# Cyusb3314_Power.net
KiCad netlist of a schematic drawn in Altium Designer
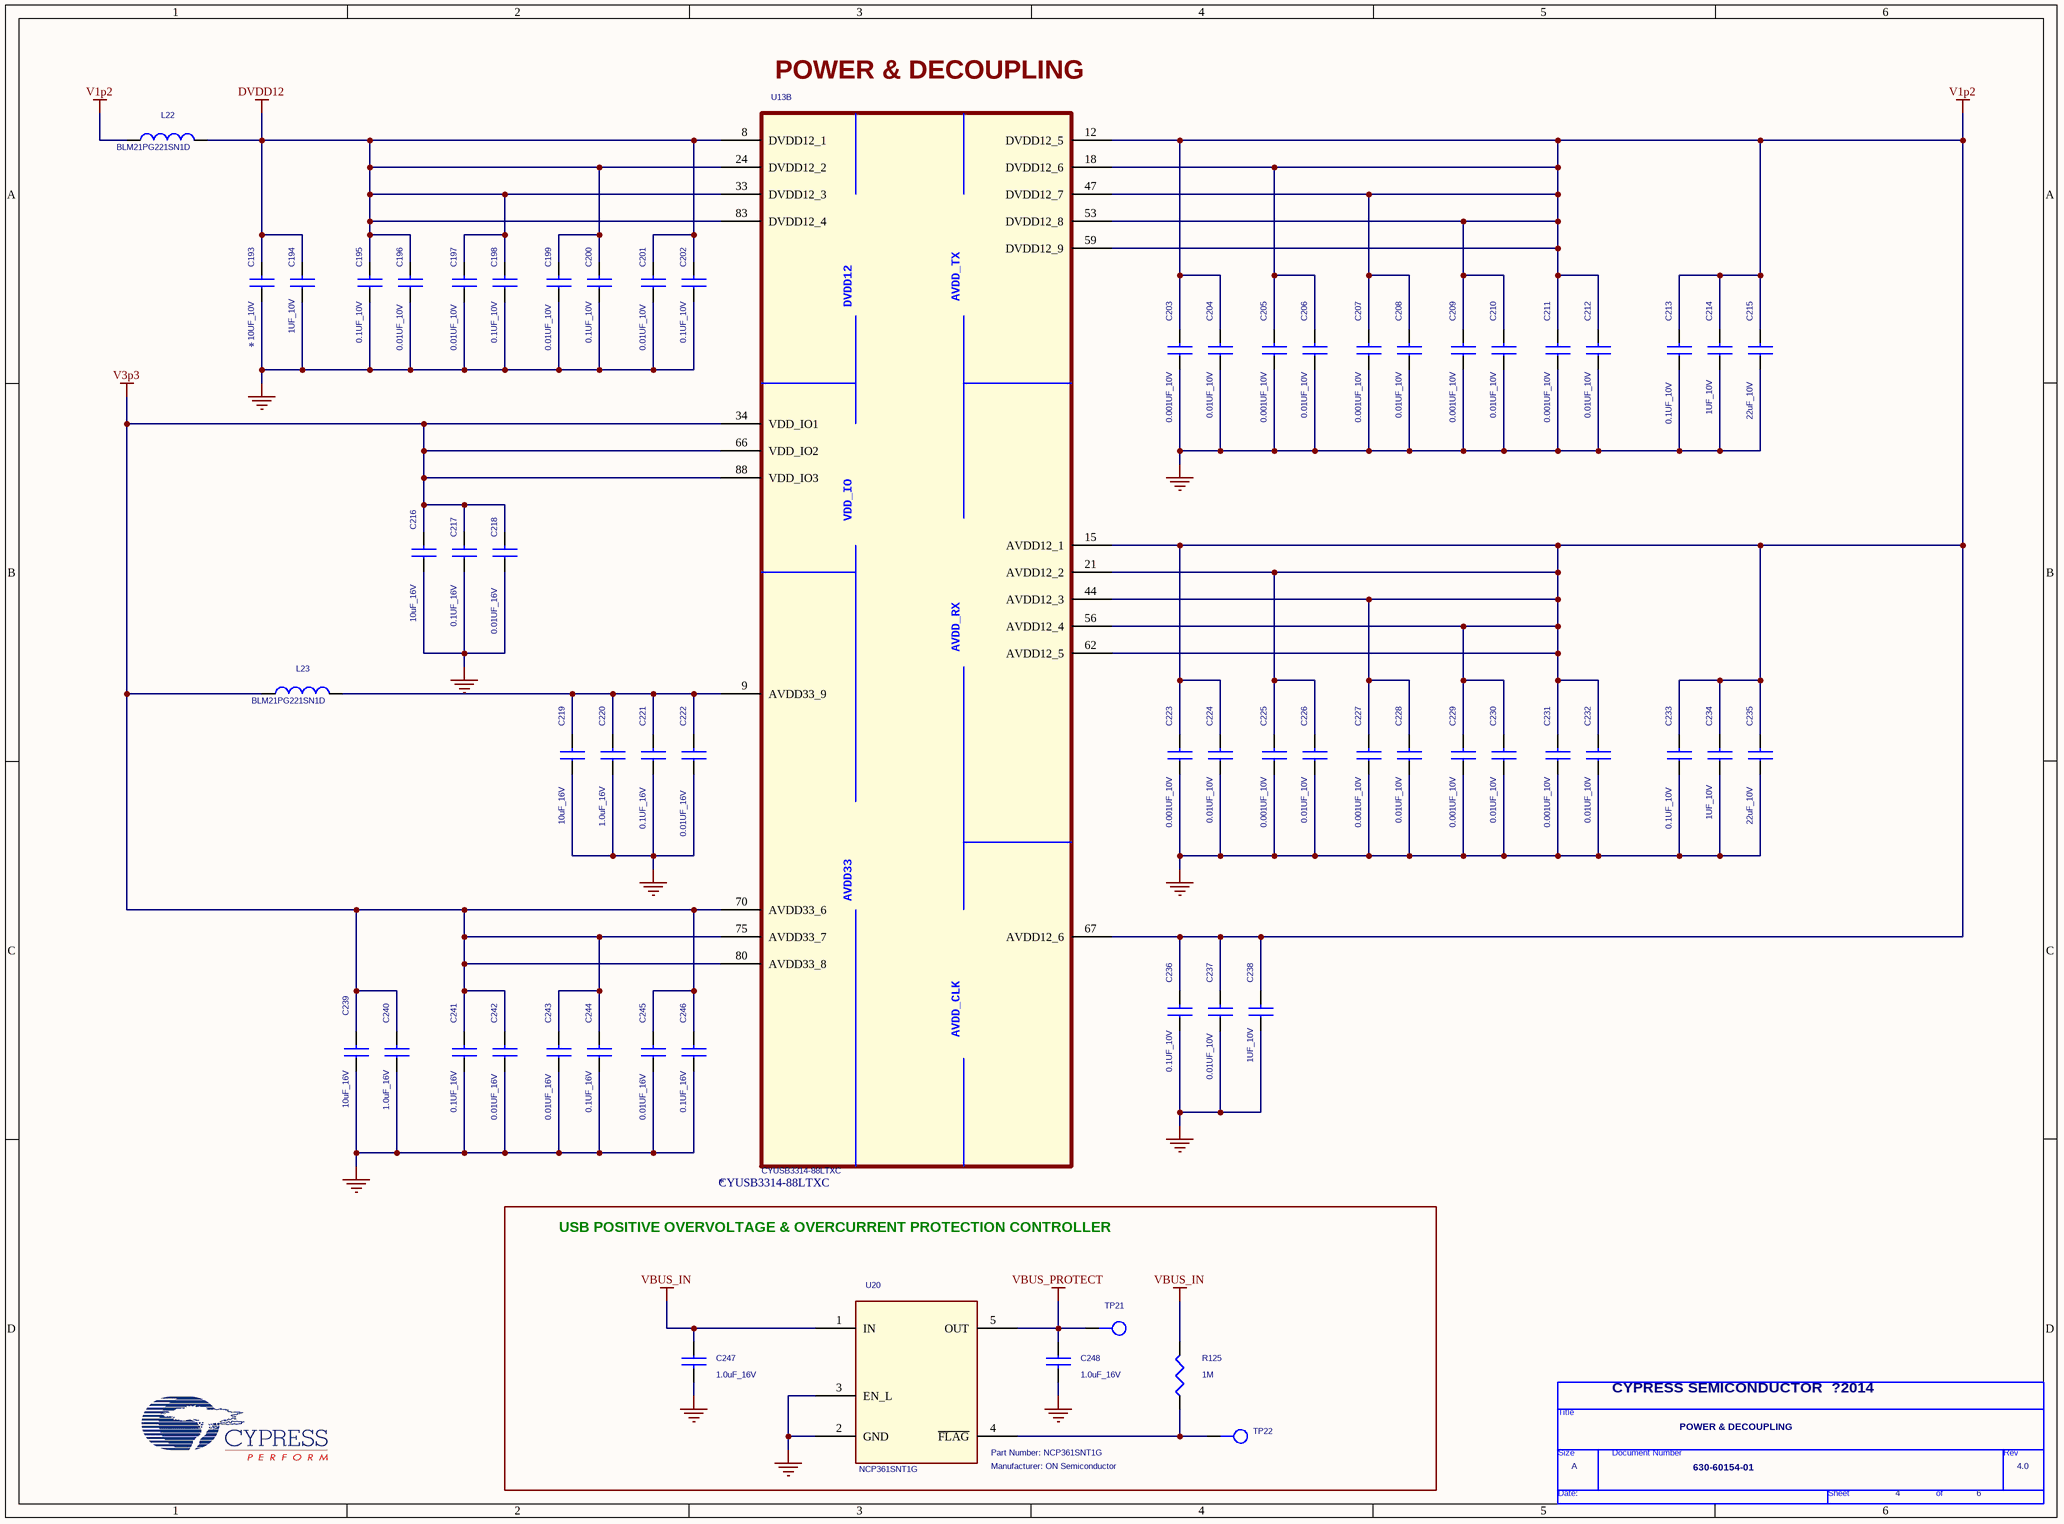
[diagram p0: Cyusb3314_Power.SchDoc]

(export (version "E")
  (design (tool "Eeschema 10.0.6"))
  (components
    (comp (ref "C193")
      (value "10UF_10V")
      (footprint "CAPC1608X90M")
      (fields (field (name "MANUFACTURER") "*"))
      (libsource (lib "*") (part "CAPACITOR NON-POL"))
    )
    (comp (ref "C194") (value "1UF_10V") (libsource (lib "*") (part "CAPACITOR NON-POL")))
    (comp (ref "C195")
      (value "0.1UF_10V")
      (footprint "CAPC1005X56M")
      (libsource (lib "*") (part "CAPACITOR NON-POL"))
    )
    (comp (ref "C196")
      (value "0.01UF_10V")
      (footprint "CAPC1005X56M")
      (libsource (lib "*") (part "CAPACITOR NON-POL"))
    )
    (comp (ref "C197")
      (value "0.01UF_10V")
      (footprint "CAPC1005X56M")
      (libsource (lib "*") (part "CAPACITOR NON-POL"))
    )
    (comp (ref "C198")
      (value "0.1UF_10V")
      (footprint "CAPC1005X56M")
      (libsource (lib "*") (part "CAPACITOR NON-POL"))
    )
    (comp (ref "C199")
      (value "0.01UF_10V")
      (footprint "CAPC1005X56M")
      (libsource (lib "*") (part "CAPACITOR NON-POL"))
    )
    (comp (ref "C200")
      (value "0.1UF_10V")
      (footprint "CAPC1005X56M")
      (libsource (lib "*") (part "CAPACITOR NON-POL"))
    )
    (comp (ref "C201")
      (value "0.01UF_10V")
      (footprint "CAPC1005X56M")
      (libsource (lib "*") (part "CAPACITOR NON-POL"))
    )
    (comp (ref "C202")
      (value "0.1UF_10V")
      (footprint "CAPC1005X56M")
      (libsource (lib "*") (part "CAPACITOR NON-POL"))
    )
    (comp (ref "C203")
      (value "0.001UF_10V")
      (footprint "CAPC1005X56M")
      (libsource (lib "*") (part "CAPACITOR NON-POL"))
    )
    (comp (ref "C204")
      (value "0.01UF_10V")
      (footprint "CAPC1005X56M")
      (libsource (lib "*") (part "CAPACITOR NON-POL"))
    )
    (comp (ref "C205")
      (value "0.001UF_10V")
      (footprint "CAPC1005X56M")
      (libsource (lib "*") (part "CAPACITOR NON-POL"))
    )
    (comp (ref "C206")
      (value "0.01UF_10V")
      (footprint "CAPC1005X56M")
      (libsource (lib "*") (part "CAPACITOR NON-POL"))
    )
    (comp (ref "C207")
      (value "0.001UF_10V")
      (footprint "CAPC1005X56M")
      (libsource (lib "*") (part "CAPACITOR NON-POL"))
    )
    (comp (ref "C208")
      (value "0.01UF_10V")
      (footprint "CAPC1005X56M")
      (libsource (lib "*") (part "CAPACITOR NON-POL"))
    )
    (comp (ref "C209")
      (value "0.001UF_10V")
      (footprint "CAPC1005X56M")
      (libsource (lib "*") (part "CAPACITOR NON-POL"))
    )
    (comp (ref "C210")
      (value "0.01UF_10V")
      (footprint "CAPC1005X56M")
      (libsource (lib "*") (part "CAPACITOR NON-POL"))
    )
    (comp (ref "C211")
      (value "0.001UF_10V")
      (footprint "CAPC1005X56M")
      (libsource (lib "*") (part "CAPACITOR NON-POL"))
    )
    (comp (ref "C212")
      (value "0.01UF_10V")
      (footprint "CAPC1005X56M")
      (libsource (lib "*") (part "CAPACITOR NON-POL"))
    )
    (comp (ref "C213")
      (value "0.1UF_10V")
      (footprint "CAPC1005X56M")
      (libsource (lib "*") (part "CAPACITOR NON-POL"))
    )
    (comp (ref "C214") (value "1UF_10V") (libsource (lib "*") (part "CAPACITOR NON-POL")))
    (comp (ref "C215") (value "22uF_10V") (libsource (lib "*") (part "CAPACITOR NON-POL")))
    (comp (ref "C216")
      (value "10uF_16V")
      (footprint "CAPC1608X90M")
      (libsource (lib "*") (part "CAPACITOR NON-POL"))
    )
    (comp (ref "C217")
      (value "0.1UF_16V")
      (footprint "CAPC1005X56M")
      (libsource (lib "*") (part "CAPACITOR NON-POL"))
    )
    (comp (ref "C218")
      (value "0.01UF_16V")
      (footprint "CAPC1005X56M")
      (libsource (lib "*") (part "CAPACITOR NON-POL"))
    )
    (comp (ref "C219")
      (value "10uF_16V")
      (footprint "CAPC1608X90M")
      (libsource (lib "*") (part "CAPACITOR NON-POL"))
    )
    (comp (ref "C220")
      (value "1.0uF_16V")
      (footprint "CAPC1005X56M")
      (libsource (lib "*") (part "CAPACITOR NON-POL"))
    )
    (comp (ref "C221")
      (value "0.1UF_16V")
      (footprint "CAPC1005X56M")
      (libsource (lib "*") (part "CAPACITOR NON-POL"))
    )
    (comp (ref "C222")
      (value "0.01UF_16V")
      (footprint "CAPC1005X56M")
      (libsource (lib "*") (part "CAPACITOR NON-POL"))
    )
    (comp (ref "C223")
      (value "0.001UF_10V")
      (footprint "CAPC1005X56M")
      (libsource (lib "*") (part "CAPACITOR NON-POL"))
    )
    (comp (ref "C224")
      (value "0.01UF_10V")
      (footprint "CAPC1005X56M")
      (libsource (lib "*") (part "CAPACITOR NON-POL"))
    )
    (comp (ref "C225")
      (value "0.001UF_10V")
      (footprint "CAPC1005X56M")
      (libsource (lib "*") (part "CAPACITOR NON-POL"))
    )
    (comp (ref "C226")
      (value "0.01UF_10V")
      (footprint "CAPC1005X56M")
      (libsource (lib "*") (part "CAPACITOR NON-POL"))
    )
    (comp (ref "C227")
      (value "0.001UF_10V")
      (footprint "CAPC1005X56M")
      (libsource (lib "*") (part "CAPACITOR NON-POL"))
    )
    (comp (ref "C228")
      (value "0.01UF_10V")
      (footprint "CAPC1005X56M")
      (libsource (lib "*") (part "CAPACITOR NON-POL"))
    )
    (comp (ref "C229")
      (value "0.001UF_10V")
      (footprint "CAPC1005X56M")
      (libsource (lib "*") (part "CAPACITOR NON-POL"))
    )
    (comp (ref "C230")
      (value "0.01UF_10V")
      (footprint "CAPC1005X56M")
      (libsource (lib "*") (part "CAPACITOR NON-POL"))
    )
    (comp (ref "C231")
      (value "0.001UF_10V")
      (footprint "CAPC1005X56M")
      (libsource (lib "*") (part "CAPACITOR NON-POL"))
    )
    (comp (ref "C232")
      (value "0.01UF_10V")
      (footprint "CAPC1005X56M")
      (libsource (lib "*") (part "CAPACITOR NON-POL"))
    )
    (comp (ref "C233")
      (value "0.1UF_10V")
      (footprint "CAPC1005X56M")
      (libsource (lib "*") (part "CAPACITOR NON-POL"))
    )
    (comp (ref "C234") (value "1UF_10V") (libsource (lib "*") (part "CAPACITOR NON-POL")))
    (comp (ref "C235") (value "22uF_10V") (libsource (lib "*") (part "CAPACITOR NON-POL")))
    (comp (ref "C236")
      (value "0.1UF_10V")
      (footprint "CAPC1005X56M")
      (libsource (lib "*") (part "CAPACITOR NON-POL"))
    )
    (comp (ref "C237")
      (value "0.01UF_10V")
      (footprint "CAPC1005X56M")
      (libsource (lib "*") (part "CAPACITOR NON-POL"))
    )
    (comp (ref "C238") (value "1UF_10V") (libsource (lib "*") (part "CAPACITOR NON-POL")))
    (comp (ref "C239")
      (value "10uF_16V")
      (footprint "CAPC1608X90M")
      (libsource (lib "*") (part "CAPACITOR NON-POL"))
    )
    (comp (ref "C240")
      (value "1.0uF_16V")
      (footprint "CAPC1005X56M")
      (libsource (lib "*") (part "CAPACITOR NON-POL"))
    )
    (comp (ref "C241")
      (value "0.1UF_16V")
      (footprint "CAPC1005X56M")
      (libsource (lib "*") (part "CAPACITOR NON-POL"))
    )
    (comp (ref "C242")
      (value "0.01UF_16V")
      (footprint "CAPC1005X56M")
      (libsource (lib "*") (part "CAPACITOR NON-POL"))
    )
    (comp (ref "C243")
      (value "0.01UF_16V")
      (footprint "CAPC1005X56M")
      (libsource (lib "*") (part "CAPACITOR NON-POL"))
    )
    (comp (ref "C244")
      (value "0.1UF_16V")
      (footprint "CAPC1005X56M")
      (libsource (lib "*") (part "CAPACITOR NON-POL"))
    )
    (comp (ref "C245")
      (value "0.01UF_16V")
      (footprint "CAPC1005X56M")
      (libsource (lib "*") (part "CAPACITOR NON-POL"))
    )
    (comp (ref "C246")
      (value "0.1UF_16V")
      (footprint "CAPC1005X56M")
      (libsource (lib "*") (part "CAPACITOR NON-POL"))
    )
    (comp (ref "C247")
      (value "1.0uF_16V")
      (footprint "CAPC1608X90M")
      (description "CAP - CER, 1uF, 10V, +/-10%, X5R, 0402")
      (libsource (lib "*") (part "CAP"))
    )
    (comp (ref "C248")
      (value "1.0uF_16V")
      (footprint "CAPC1608X90M")
      (description "CAP - CER, 1uF, 10V, +/-10%, X5R, 0402")
      (libsource (lib "*") (part "CAP"))
    )
    (comp (ref "L22")
      (value "BLM21PG221SN1D")
      (description "FERRITE CHIP 220 OHM 2A 0805")
      (fields (field (name "MANUFACTURER") "Murata"))
      (libsource (lib "*") (part "INDUCTOR"))
    )
    (comp (ref "L23")
      (value "BLM21PG221SN1D")
      (description "FERRITE CHIP 220 OHM 2A 0805")
      (fields (field (name "MANUFACTURER") "Murata"))
      (libsource (lib "*") (part "INDUCTOR"))
    )
    (comp (ref "R125")
      (value "1M")
      (description "RES 1.00M OHM 1/10W 1% 0402 SMD")
      (fields (field (name "MANUFACTURER") "Panasonic") (field (name "PART NUMBER") "ERJ-2RKF1004X"))
      (libsource (lib "*") (part "R"))
    )
    (comp (ref "TP21")
      (value "TP_RED")
      (footprint "KEYSTONE_5000")
      (description "TEST POINT PC MINI .040\"D RED")
      (fields (field (name "PART_NUMBER") "5000") (field (name "MANUFACTURER") "Keystone"))
      (libsource (lib "*") (part "TP"))
    )
    (comp (ref "TP22")
      (value "TP_YEL")
      (footprint "KEYSTONE_5000")
      (description "TEST POINT PC MINI .040\"D RED")
      (fields (field (name "MANUFACTURER") "Keystone") (field (name "PART_NUMBER") "5000"))
      (libsource (lib "*") (part "TP"))
    )
    (comp (ref "U13")
      (value "CYUSB3314-88LTXC")
      (footprint "QFN40P1000X1000X100-89M")
      (fields (field (name "MANUFACTURER") "*") (field (name "PART NUMBER") "CYUSB3314-88LTXC"))
      (libsource (lib "*") (part "CYUSB3314-88LTXC_2"))
    )
    (comp (ref "U20")
      (value "NCP361SNT1G")
      (footprint "SOP95P275X110-5M")
      (description "IC USB POS OVP/OC_TSOP5")
      (fields (field (name "MANUFACTURER") "ON Semiconductor") (field (name "PART NUMBER") "NCP361SNT1G"))
      (libsource (lib "*") (part "NCP361SNT1G_0"))
    )
  )
  (nets
    (net (code "1") (name "DVDD12") (class "Default")
      (node (ref "C193") (pin "2") (pinfunction "2_2") (pintype "passive"))
      (node (ref "C194") (pin "2") (pinfunction "2_2") (pintype "passive"))
      (node (ref "C195") (pin "2") (pinfunction "2_2") (pintype "passive"))
      (node (ref "C196") (pin "2") (pinfunction "2_2") (pintype "passive"))
      (node (ref "C197") (pin "2") (pinfunction "2_2") (pintype "passive"))
      (node (ref "C198") (pin "2") (pinfunction "2_2") (pintype "passive"))
      (node (ref "C199") (pin "2") (pinfunction "2_2") (pintype "passive"))
      (node (ref "C200") (pin "2") (pinfunction "2_2") (pintype "passive"))
      (node (ref "C201") (pin "2") (pinfunction "2_2") (pintype "passive"))
      (node (ref "C202") (pin "2") (pinfunction "2_2") (pintype "passive"))
      (node (ref "L22") (pin "2") (pinfunction "2_2") (pintype "passive"))
      (node (ref "U13") (pin "24") (pinfunction "DVDD12_2_24") (pintype "passive"))
      (node (ref "U13") (pin "33") (pinfunction "DVDD12_3_33") (pintype "passive"))
      (node (ref "U13") (pin "8") (pinfunction "DVDD12_1_8") (pintype "passive"))
      (node (ref "U13") (pin "83") (pinfunction "DVDD12_4_83") (pintype "passive"))
    )
    (net (code "2") (name "GND") (class "Default")
      (node (ref "C193") (pin "1") (pinfunction "1_1") (pintype "passive"))
      (node (ref "C194") (pin "1") (pinfunction "1_1") (pintype "passive"))
      (node (ref "C195") (pin "1") (pinfunction "1_1") (pintype "passive"))
      (node (ref "C196") (pin "1") (pinfunction "1_1") (pintype "passive"))
      (node (ref "C197") (pin "1") (pinfunction "1_1") (pintype "passive"))
      (node (ref "C198") (pin "1") (pinfunction "1_1") (pintype "passive"))
      (node (ref "C199") (pin "1") (pinfunction "1_1") (pintype "passive"))
      (node (ref "C200") (pin "1") (pinfunction "1_1") (pintype "passive"))
      (node (ref "C201") (pin "1") (pinfunction "1_1") (pintype "passive"))
      (node (ref "C202") (pin "1") (pinfunction "1_1") (pintype "passive"))
      (node (ref "C203") (pin "1") (pinfunction "1_1") (pintype "passive"))
      (node (ref "C204") (pin "1") (pinfunction "1_1") (pintype "passive"))
      (node (ref "C205") (pin "1") (pinfunction "1_1") (pintype "passive"))
      (node (ref "C206") (pin "1") (pinfunction "1_1") (pintype "passive"))
      (node (ref "C207") (pin "1") (pinfunction "1_1") (pintype "passive"))
      (node (ref "C208") (pin "1") (pinfunction "1_1") (pintype "passive"))
      (node (ref "C209") (pin "1") (pinfunction "1_1") (pintype "passive"))
      (node (ref "C210") (pin "1") (pinfunction "1_1") (pintype "passive"))
      (node (ref "C211") (pin "1") (pinfunction "1_1") (pintype "passive"))
      (node (ref "C212") (pin "1") (pinfunction "1_1") (pintype "passive"))
      (node (ref "C213") (pin "1") (pinfunction "1_1") (pintype "passive"))
      (node (ref "C214") (pin "1") (pinfunction "1_1") (pintype "passive"))
      (node (ref "C215") (pin "1") (pinfunction "1_1") (pintype "passive"))
      (node (ref "C216") (pin "1") (pinfunction "1_1") (pintype "passive"))
      (node (ref "C217") (pin "1") (pinfunction "1_1") (pintype "passive"))
      (node (ref "C218") (pin "1") (pinfunction "1_1") (pintype "passive"))
      (node (ref "C219") (pin "1") (pinfunction "1_1") (pintype "passive"))
      (node (ref "C220") (pin "1") (pinfunction "1_1") (pintype "passive"))
      (node (ref "C221") (pin "1") (pinfunction "1_1") (pintype "passive"))
      (node (ref "C222") (pin "1") (pinfunction "1_1") (pintype "passive"))
      (node (ref "C223") (pin "1") (pinfunction "1_1") (pintype "passive"))
      (node (ref "C224") (pin "1") (pinfunction "1_1") (pintype "passive"))
      (node (ref "C225") (pin "1") (pinfunction "1_1") (pintype "passive"))
      (node (ref "C226") (pin "1") (pinfunction "1_1") (pintype "passive"))
      (node (ref "C227") (pin "1") (pinfunction "1_1") (pintype "passive"))
      (node (ref "C228") (pin "1") (pinfunction "1_1") (pintype "passive"))
      (node (ref "C229") (pin "1") (pinfunction "1_1") (pintype "passive"))
      (node (ref "C230") (pin "1") (pinfunction "1_1") (pintype "passive"))
      (node (ref "C231") (pin "1") (pinfunction "1_1") (pintype "passive"))
      (node (ref "C232") (pin "1") (pinfunction "1_1") (pintype "passive"))
      (node (ref "C233") (pin "1") (pinfunction "1_1") (pintype "passive"))
      (node (ref "C234") (pin "1") (pinfunction "1_1") (pintype "passive"))
      (node (ref "C235") (pin "1") (pinfunction "1_1") (pintype "passive"))
      (node (ref "C236") (pin "1") (pinfunction "1_1") (pintype "passive"))
      (node (ref "C237") (pin "1") (pinfunction "1_1") (pintype "passive"))
      (node (ref "C238") (pin "1") (pinfunction "1_1") (pintype "passive"))
      (node (ref "C239") (pin "1") (pinfunction "1_1") (pintype "passive"))
      (node (ref "C240") (pin "1") (pinfunction "1_1") (pintype "passive"))
      (node (ref "C241") (pin "1") (pinfunction "1_1") (pintype "passive"))
      (node (ref "C242") (pin "1") (pinfunction "1_1") (pintype "passive"))
      (node (ref "C243") (pin "1") (pinfunction "1_1") (pintype "passive"))
      (node (ref "C244") (pin "1") (pinfunction "1_1") (pintype "passive"))
      (node (ref "C245") (pin "1") (pinfunction "1_1") (pintype "passive"))
      (node (ref "C246") (pin "1") (pinfunction "1_1") (pintype "passive"))
      (node (ref "C247") (pin "2") (pinfunction "2_2") (pintype "passive"))
      (node (ref "C248") (pin "2") (pinfunction "2_2") (pintype "passive"))
      (node (ref "U20") (pin "2") (pinfunction "GND_2") (pintype "passive"))
      (node (ref "U20") (pin "3") (pinfunction "EN_L_3") (pintype "passive"))
    )
    (net (code "3") (name "Net-(TP22-TP)") (class "Default")
      (node (ref "R125") (pin "1") (pinfunction "1_1") (pintype "passive"))
      (node (ref "TP22") (pin "1") (pinfunction "TP_1") (pintype "passive"))
      (node (ref "U20") (pin "4") (pinfunction "~{FLAG}_4") (pintype "passive"))
    )
    (net (code "4") (name "Net-(U13B-AVDD33_9)") (class "Default")
      (node (ref "C219") (pin "2") (pinfunction "2_2") (pintype "passive"))
      (node (ref "C220") (pin "2") (pinfunction "2_2") (pintype "passive"))
      (node (ref "C221") (pin "2") (pinfunction "2_2") (pintype "passive"))
      (node (ref "C222") (pin "2") (pinfunction "2_2") (pintype "passive"))
      (node (ref "L23") (pin "2") (pinfunction "2_2") (pintype "passive"))
      (node (ref "U13") (pin "9") (pinfunction "AVDD33_9_9") (pintype "passive"))
    )
    (net (code "5") (name "V1p2") (class "Default")
      (node (ref "C203") (pin "2") (pinfunction "2_2") (pintype "passive"))
      (node (ref "C204") (pin "2") (pinfunction "2_2") (pintype "passive"))
      (node (ref "C205") (pin "2") (pinfunction "2_2") (pintype "passive"))
      (node (ref "C206") (pin "2") (pinfunction "2_2") (pintype "passive"))
      (node (ref "C207") (pin "2") (pinfunction "2_2") (pintype "passive"))
      (node (ref "C208") (pin "2") (pinfunction "2_2") (pintype "passive"))
      (node (ref "C209") (pin "2") (pinfunction "2_2") (pintype "passive"))
      (node (ref "C210") (pin "2") (pinfunction "2_2") (pintype "passive"))
      (node (ref "C211") (pin "2") (pinfunction "2_2") (pintype "passive"))
      (node (ref "C212") (pin "2") (pinfunction "2_2") (pintype "passive"))
      (node (ref "C213") (pin "2") (pinfunction "2_2") (pintype "passive"))
      (node (ref "C214") (pin "2") (pinfunction "2_2") (pintype "passive"))
      (node (ref "C215") (pin "2") (pinfunction "2_2") (pintype "passive"))
      (node (ref "C223") (pin "2") (pinfunction "2_2") (pintype "passive"))
      (node (ref "C224") (pin "2") (pinfunction "2_2") (pintype "passive"))
      (node (ref "C225") (pin "2") (pinfunction "2_2") (pintype "passive"))
      (node (ref "C226") (pin "2") (pinfunction "2_2") (pintype "passive"))
      (node (ref "C227") (pin "2") (pinfunction "2_2") (pintype "passive"))
      (node (ref "C228") (pin "2") (pinfunction "2_2") (pintype "passive"))
      (node (ref "C229") (pin "2") (pinfunction "2_2") (pintype "passive"))
      (node (ref "C230") (pin "2") (pinfunction "2_2") (pintype "passive"))
      (node (ref "C231") (pin "2") (pinfunction "2_2") (pintype "passive"))
      (node (ref "C232") (pin "2") (pinfunction "2_2") (pintype "passive"))
      (node (ref "C233") (pin "2") (pinfunction "2_2") (pintype "passive"))
      (node (ref "C234") (pin "2") (pinfunction "2_2") (pintype "passive"))
      (node (ref "C235") (pin "2") (pinfunction "2_2") (pintype "passive"))
      (node (ref "C236") (pin "2") (pinfunction "2_2") (pintype "passive"))
      (node (ref "C237") (pin "2") (pinfunction "2_2") (pintype "passive"))
      (node (ref "C238") (pin "2") (pinfunction "2_2") (pintype "passive"))
      (node (ref "L22") (pin "1") (pinfunction "1_1") (pintype "passive"))
      (node (ref "U13") (pin "12") (pinfunction "DVDD12_5_12") (pintype "passive"))
      (node (ref "U13") (pin "15") (pinfunction "AVDD12_1_15") (pintype "passive"))
      (node (ref "U13") (pin "18") (pinfunction "DVDD12_6_18") (pintype "passive"))
      (node (ref "U13") (pin "21") (pinfunction "AVDD12_2_21") (pintype "passive"))
      (node (ref "U13") (pin "44") (pinfunction "AVDD12_3_44") (pintype "passive"))
      (node (ref "U13") (pin "47") (pinfunction "DVDD12_7_47") (pintype "passive"))
      (node (ref "U13") (pin "53") (pinfunction "DVDD12_8_53") (pintype "passive"))
      (node (ref "U13") (pin "56") (pinfunction "AVDD12_4_56") (pintype "passive"))
      (node (ref "U13") (pin "59") (pinfunction "DVDD12_9_59") (pintype "passive"))
      (node (ref "U13") (pin "62") (pinfunction "AVDD12_5_62") (pintype "passive"))
      (node (ref "U13") (pin "67") (pinfunction "AVDD12_6_67") (pintype "passive"))
    )
    (net (code "6") (name "V3p3") (class "Default")
      (node (ref "C216") (pin "2") (pinfunction "2_2") (pintype "passive"))
      (node (ref "C217") (pin "2") (pinfunction "2_2") (pintype "passive"))
      (node (ref "C218") (pin "2") (pinfunction "2_2") (pintype "passive"))
      (node (ref "C239") (pin "2") (pinfunction "2_2") (pintype "passive"))
      (node (ref "C240") (pin "2") (pinfunction "2_2") (pintype "passive"))
      (node (ref "C241") (pin "2") (pinfunction "2_2") (pintype "passive"))
      (node (ref "C242") (pin "2") (pinfunction "2_2") (pintype "passive"))
      (node (ref "C243") (pin "2") (pinfunction "2_2") (pintype "passive"))
      (node (ref "C244") (pin "2") (pinfunction "2_2") (pintype "passive"))
      (node (ref "C245") (pin "2") (pinfunction "2_2") (pintype "passive"))
      (node (ref "C246") (pin "2") (pinfunction "2_2") (pintype "passive"))
      (node (ref "L23") (pin "1") (pinfunction "1_1") (pintype "passive"))
      (node (ref "U13") (pin "34") (pinfunction "VDD_IO1_34") (pintype "passive"))
      (node (ref "U13") (pin "66") (pinfunction "VDD_IO2_66") (pintype "passive"))
      (node (ref "U13") (pin "70") (pinfunction "AVDD33_6_70") (pintype "passive"))
      (node (ref "U13") (pin "75") (pinfunction "AVDD33_7_75") (pintype "passive"))
      (node (ref "U13") (pin "80") (pinfunction "AVDD33_8_80") (pintype "passive"))
      (node (ref "U13") (pin "88") (pinfunction "VDD_IO3_88") (pintype "passive"))
    )
    (net (code "7") (name "VBUS_IN") (class "Default")
      (node (ref "C247") (pin "1") (pinfunction "1_1") (pintype "passive"))
      (node (ref "R125") (pin "2") (pinfunction "2_2") (pintype "passive"))
      (node (ref "U20") (pin "1") (pinfunction "IN_1") (pintype "passive"))
    )
    (net (code "8") (name "VBUS_PROTECT") (class "Default")
      (node (ref "C248") (pin "1") (pinfunction "1_1") (pintype "passive"))
      (node (ref "TP21") (pin "1") (pinfunction "TP_1") (pintype "passive"))
      (node (ref "U20") (pin "5") (pinfunction "OUT_5") (pintype "passive"))
    )
  )
)
